# untitled.net
KiCad netlist of a schematic drawn in EAGLE
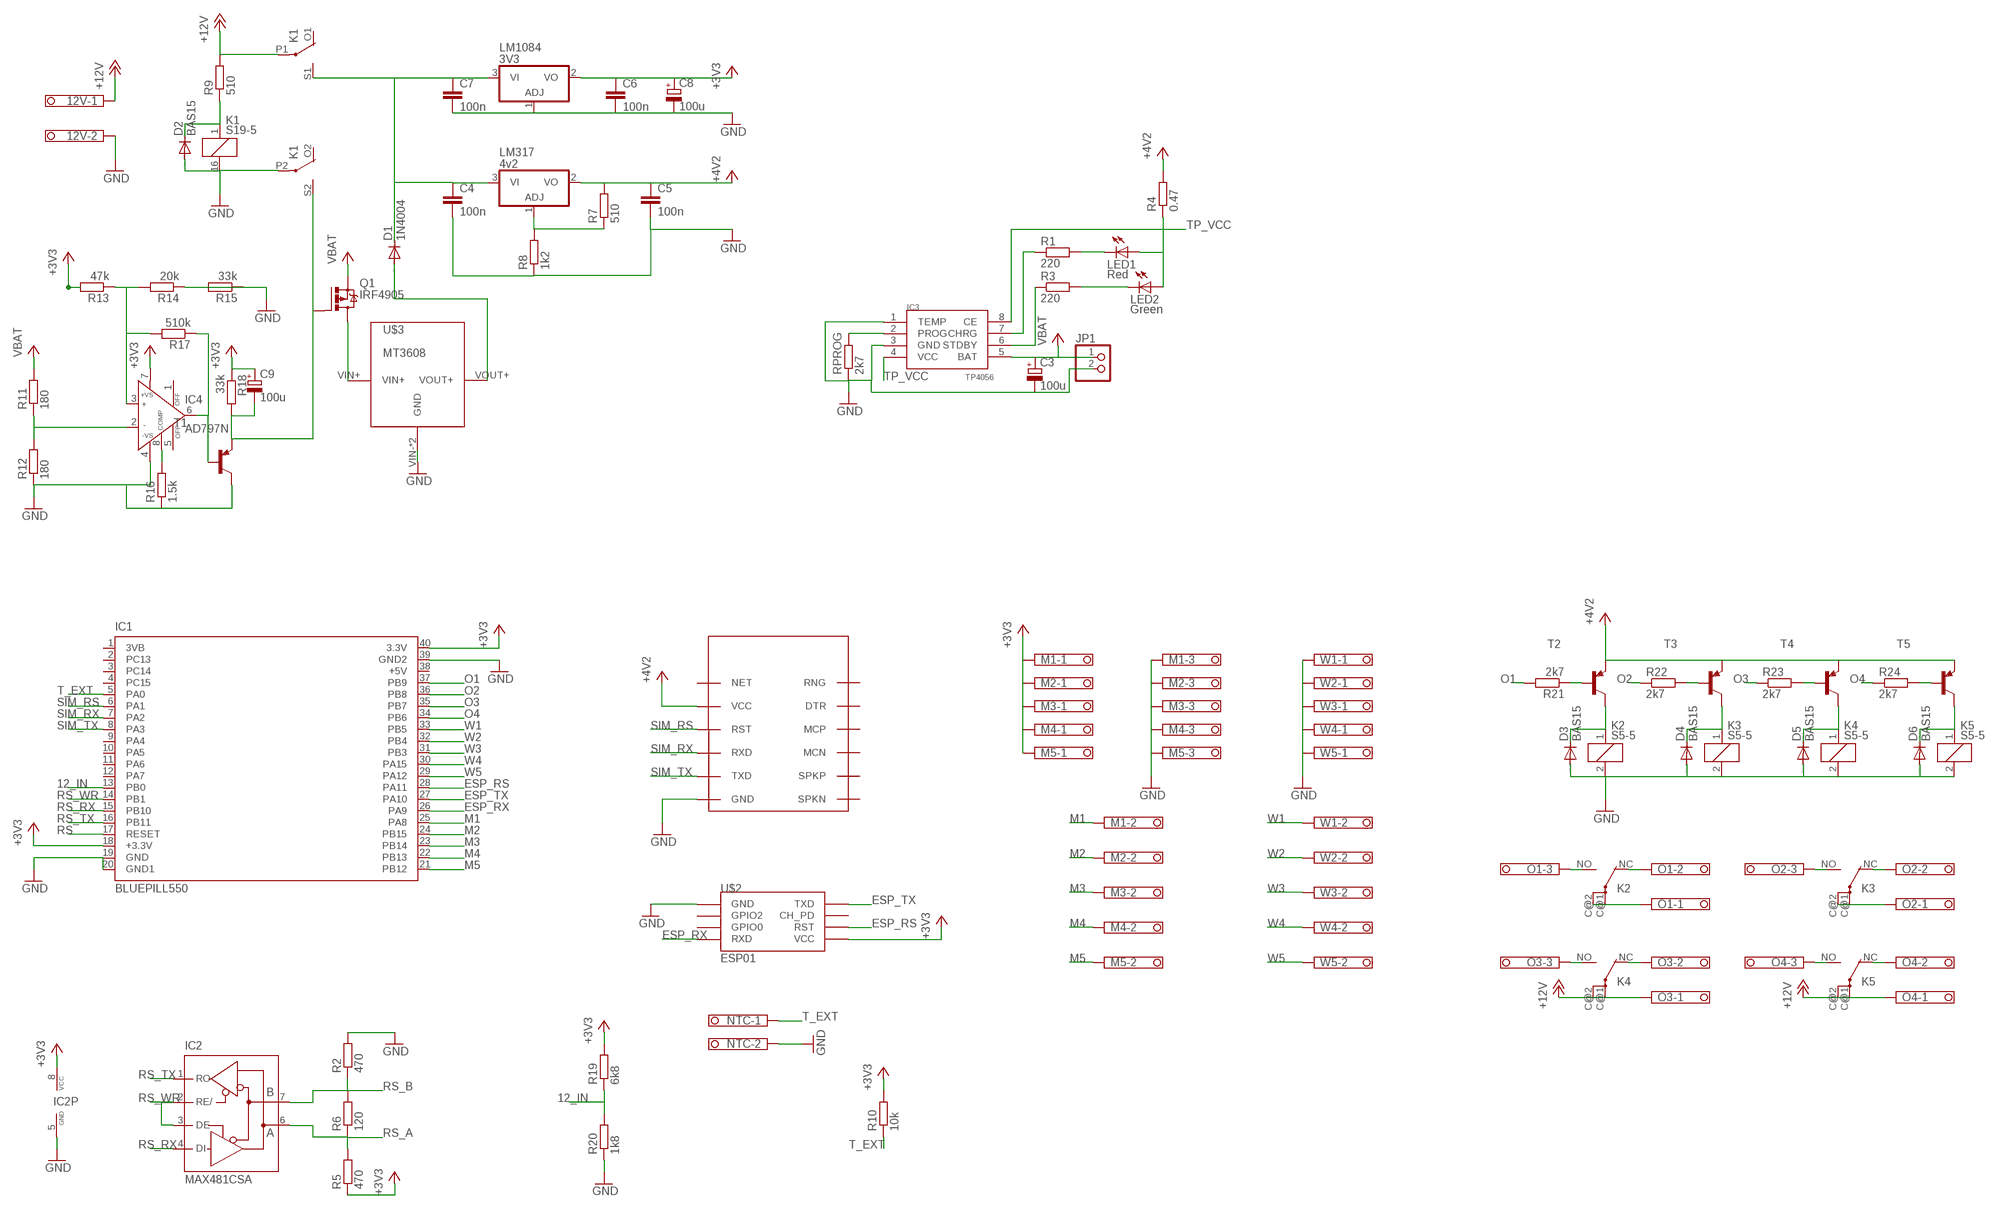
[diagram p0: schematic, sheet 1]

(export (version "E")
  (design (tool "Eeschema 10.0.6"))
  (components
    (comp (ref "12V")
      (value "1751248")
      (footprint "eagle-import:1751248")
      (libsource (lib "eagle-import") (part "1751248"))
    )
    (comp (ref "C3")
      (value "100u")
      (footprint "eagle-import:E2,5-6E")
      (libsource (lib "eagle-import") (part "CPOL-EUE2,5-6E"))
    )
    (comp (ref "C4")
      (value "100n")
      (footprint "eagle-import:C2012")
      (libsource (lib "eagle-import") (part "C-EUC2012"))
    )
    (comp (ref "C5")
      (value "100n")
      (footprint "eagle-import:C2012")
      (libsource (lib "eagle-import") (part "C-EUC2012"))
    )
    (comp (ref "C6")
      (value "100n")
      (footprint "eagle-import:C2012")
      (libsource (lib "eagle-import") (part "C-EUC2012"))
    )
    (comp (ref "C7")
      (value "100n")
      (footprint "eagle-import:C2012")
      (libsource (lib "eagle-import") (part "C-EUC2012"))
    )
    (comp (ref "C8")
      (value "100u")
      (footprint "eagle-import:E2,5-6E")
      (libsource (lib "eagle-import") (part "CPOL-EUE2,5-6E"))
    )
    (comp (ref "C9")
      (value "100u")
      (footprint "eagle-import:E2,5-6E")
      (libsource (lib "eagle-import") (part "CPOL-EUE2,5-6E"))
    )
    (comp (ref "D1")
      (value "1N4004")
      (footprint "eagle-import:DO41-10")
      (libsource (lib "eagle-import") (part "1N4004"))
    )
    (comp (ref "D2")
      (value "BAS15")
      (footprint "eagle-import:DO34-7")
      (libsource (lib "eagle-import") (part "BAS15"))
    )
    (comp (ref "D3")
      (value "BAS15")
      (footprint "eagle-import:DO34-7")
      (libsource (lib "eagle-import") (part "BAS15"))
    )
    (comp (ref "D4")
      (value "BAS15")
      (footprint "eagle-import:DO34-7")
      (libsource (lib "eagle-import") (part "BAS15"))
    )
    (comp (ref "D5")
      (value "BAS15")
      (footprint "eagle-import:DO34-7")
      (libsource (lib "eagle-import") (part "BAS15"))
    )
    (comp (ref "D6")
      (value "BAS15")
      (footprint "eagle-import:DO34-7")
      (libsource (lib "eagle-import") (part "BAS15"))
    )
    (comp (ref "IC1")
      (value "BLUEPILL550")
      (footprint "eagle-import:DIL40")
      (fields (field (name "MF") "BluePill"))
      (libsource (lib "eagle-import") (part "BLUEPILL550"))
    )
    (comp (ref "IC2")
      (value "MAX481CSA")
      (footprint "eagle-import:SO08")
      (fields (field (name "MF") "MAXIM"))
      (libsource (lib "eagle-import") (part "MAX481CSA"))
    )
    (comp (ref "IC3")
      (value "TP4056")
      (footprint "eagle-import:SOP-8")
      (libsource (lib "eagle-import") (part "TP4056"))
    )
    (comp (ref "IC4")
      (value "AD797N")
      (footprint "eagle-import:DIL08")
      (fields (field (name "MF") "ALTERA CORPORATION") (field (name "MPN") "AD797ANZ"))
      (libsource (lib "eagle-import") (part "AD797N"))
    )
    (comp (ref "JP1")
      (value "PINHD-1X2")
      (footprint "eagle-import:1X02")
      (libsource (lib "eagle-import") (part "PINHD-1X2"))
    )
    (comp (ref "K1")
      (value "S19-5")
      (footprint "eagle-import:351")
      (libsource (lib "eagle-import") (part "351"))
    )
    (comp (ref "K2")
      (value "S5-5")
      (footprint "eagle-import:HY")
      (fields (field (name "MF") "AROMAT/ MATSUSHITA") (field (name "MPN") "HY1-5V"))
      (libsource (lib "eagle-import") (part "HY1-5V"))
    )
    (comp (ref "K3")
      (value "S5-5")
      (footprint "eagle-import:HY")
      (fields (field (name "MF") "AROMAT/ MATSUSHITA") (field (name "MPN") "HY1-5V"))
      (libsource (lib "eagle-import") (part "HY1-5V"))
    )
    (comp (ref "K4")
      (value "S5-5")
      (footprint "eagle-import:HY")
      (fields (field (name "MF") "AROMAT/ MATSUSHITA") (field (name "MPN") "HY1-5V"))
      (libsource (lib "eagle-import") (part "HY1-5V"))
    )
    (comp (ref "K5")
      (value "S5-5")
      (footprint "eagle-import:HY")
      (fields (field (name "MF") "AROMAT/ MATSUSHITA") (field (name "MPN") "HY1-5V"))
      (libsource (lib "eagle-import") (part "HY1-5V"))
    )
    (comp (ref "LED1")
      (value "Red")
      (footprint "eagle-import:CHIP-LED0805")
      (libsource (lib "eagle-import") (part "LEDCHIP-LED0805"))
    )
    (comp (ref "LED2")
      (value "Green")
      (footprint "eagle-import:CHIP-LED0805")
      (libsource (lib "eagle-import") (part "LEDCHIP-LED0805"))
    )
    (comp (ref "LM317")
      (value "4v2")
      (footprint "eagle-import:TO220H")
      (libsource (lib "eagle-import") (part "317T"))
    )
    (comp (ref "LM1084")
      (value "3V3")
      (footprint "eagle-import:TO220H")
      (libsource (lib "eagle-import") (part "317T"))
    )
    (comp (ref "M1")
      (value "1751251")
      (footprint "eagle-import:1751251")
      (libsource (lib "eagle-import") (part "1751251"))
    )
    (comp (ref "M2")
      (value "1751251")
      (footprint "eagle-import:1751251")
      (libsource (lib "eagle-import") (part "1751251"))
    )
    (comp (ref "M3")
      (value "1751251")
      (footprint "eagle-import:1751251")
      (libsource (lib "eagle-import") (part "1751251"))
    )
    (comp (ref "M4")
      (value "1751251")
      (footprint "eagle-import:1751251")
      (libsource (lib "eagle-import") (part "1751251"))
    )
    (comp (ref "M5")
      (value "1751251")
      (footprint "eagle-import:1751251")
      (libsource (lib "eagle-import") (part "1751251"))
    )
    (comp (ref "NTC")
      (value "1751248")
      (footprint "eagle-import:1751248")
      (libsource (lib "eagle-import") (part "1751248"))
    )
    (comp (ref "O1")
      (value "1751251")
      (footprint "eagle-import:1751251")
      (libsource (lib "eagle-import") (part "1751251"))
    )
    (comp (ref "O2")
      (value "1751251")
      (footprint "eagle-import:1751251")
      (libsource (lib "eagle-import") (part "1751251"))
    )
    (comp (ref "O3")
      (value "1751251")
      (footprint "eagle-import:1751251")
      (libsource (lib "eagle-import") (part "1751251"))
    )
    (comp (ref "O4")
      (value "1751251")
      (footprint "eagle-import:1751251")
      (libsource (lib "eagle-import") (part "1751251"))
    )
    (comp (ref "Q1")
      (value "IRF4905")
      (footprint "eagle-import:TO220BH")
      (libsource (lib "eagle-import") (part "IRF4905"))
    )
    (comp (ref "R1")
      (value "220")
      (footprint "eagle-import:R0805")
      (libsource (lib "eagle-import") (part "resistor_R-EU_R0805"))
    )
    (comp (ref "R2")
      (value "470")
      (footprint "eagle-import:0204_5")
      (libsource (lib "eagle-import") (part "resistor_R-EU_0204/5"))
    )
    (comp (ref "R3")
      (value "220")
      (footprint "eagle-import:R0805")
      (libsource (lib "eagle-import") (part "resistor_R-EU_R0805"))
    )
    (comp (ref "R4")
      (value "0.47")
      (footprint "eagle-import:0207_12")
      (libsource (lib "eagle-import") (part "resistor_R-EU_0207/12"))
    )
    (comp (ref "R5")
      (value "470")
      (footprint "eagle-import:0204_5")
      (libsource (lib "eagle-import") (part "resistor_R-EU_0204/5"))
    )
    (comp (ref "R6")
      (value "120")
      (footprint "eagle-import:0204_7")
      (libsource (lib "eagle-import") (part "resistor_R-EU_0204/7"))
    )
    (comp (ref "R7")
      (value "510")
      (footprint "eagle-import:0204_7")
      (libsource (lib "eagle-import") (part "resistor_R-EU_0204/7"))
    )
    (comp (ref "R8")
      (value "1k2")
      (footprint "eagle-import:0204_7")
      (libsource (lib "eagle-import") (part "resistor_R-EU_0204/7"))
    )
    (comp (ref "R9")
      (value "510")
      (footprint "eagle-import:0204_7")
      (libsource (lib "eagle-import") (part "resistor_R-EU_0204/7"))
    )
    (comp (ref "R10")
      (value "10k")
      (footprint "eagle-import:0204_5")
      (libsource (lib "eagle-import") (part "R-EU_0204/5"))
    )
    (comp (ref "R11")
      (value "180")
      (footprint "eagle-import:0204_7")
      (libsource (lib "eagle-import") (part "resistor_R-EU_0204/7"))
    )
    (comp (ref "R12")
      (value "180")
      (footprint "eagle-import:0204_7")
      (libsource (lib "eagle-import") (part "resistor_R-EU_0204/7"))
    )
    (comp (ref "R13")
      (value "47k")
      (footprint "eagle-import:0204_7")
      (libsource (lib "eagle-import") (part "resistor_R-EU_0204/7"))
    )
    (comp (ref "R14")
      (value "20k")
      (footprint "eagle-import:0204_7")
      (libsource (lib "eagle-import") (part "resistor_R-EU_0204/7"))
    )
    (comp (ref "R15")
      (value "33k")
      (footprint "eagle-import:0204_7")
      (libsource (lib "eagle-import") (part "resistor_R-EU_0204/7"))
    )
    (comp (ref "R16")
      (value "1.5k")
      (footprint "eagle-import:0204_7")
      (libsource (lib "eagle-import") (part "resistor_R-EU_0204/7"))
    )
    (comp (ref "R17")
      (value "510k")
      (footprint "eagle-import:0204_7")
      (libsource (lib "eagle-import") (part "resistor_R-EU_0204/7"))
    )
    (comp (ref "R18")
      (value "33k")
      (footprint "eagle-import:0204_7")
      (libsource (lib "eagle-import") (part "resistor_R-EU_0204/7"))
    )
    (comp (ref "R19")
      (value "6k8")
      (footprint "eagle-import:0204_5")
      (libsource (lib "eagle-import") (part "R-EU_0204/5"))
    )
    (comp (ref "R20")
      (value "1k8")
      (footprint "eagle-import:0204_5")
      (libsource (lib "eagle-import") (part "R-EU_0204/5"))
    )
    (comp (ref "R21")
      (value "2k7")
      (footprint "eagle-import:0204_7")
      (libsource (lib "eagle-import") (part "resistor_R-EU_0204/7"))
    )
    (comp (ref "R22")
      (value "2k7")
      (footprint "eagle-import:0204_7")
      (libsource (lib "eagle-import") (part "resistor_R-EU_0204/7"))
    )
    (comp (ref "R23")
      (value "2k7")
      (footprint "eagle-import:0204_7")
      (libsource (lib "eagle-import") (part "resistor_R-EU_0204/7"))
    )
    (comp (ref "R24")
      (value "2k7")
      (footprint "eagle-import:0204_7")
      (libsource (lib "eagle-import") (part "resistor_R-EU_0204/7"))
    )
    (comp (ref "RPROG")
      (value "2k7")
      (footprint "eagle-import:0204_7")
      (libsource (lib "eagle-import") (part "resistor_R-EU_0204/7"))
    )
    (comp (ref "T1")
      (value "BC327-40-PNP-TO92-EBC")
      (footprint "eagle-import:TO92-EBC")
      (libsource (lib "eagle-import") (part "-PNP-TO92-EBCBC327-40"))
    )
    (comp (ref "T2")
      (value "BC327-40-PNP-TO92-EBC")
      (footprint "eagle-import:TO92-EBC")
      (libsource (lib "eagle-import") (part "-PNP-TO92-EBCBC327-40"))
    )
    (comp (ref "T3")
      (value "BC327-40-PNP-TO92-EBC")
      (footprint "eagle-import:TO92-EBC")
      (libsource (lib "eagle-import") (part "-PNP-TO92-EBCBC327-40"))
    )
    (comp (ref "T4")
      (value "BC327-40-PNP-TO92-EBC")
      (footprint "eagle-import:TO92-EBC")
      (libsource (lib "eagle-import") (part "-PNP-TO92-EBCBC327-40"))
    )
    (comp (ref "T5")
      (value "BC327-40-PNP-TO92-EBC")
      (footprint "eagle-import:TO92-EBC")
      (libsource (lib "eagle-import") (part "-PNP-TO92-EBCBC327-40"))
    )
    (comp (ref "U$1")
      (value "SIM800L")
      (footprint "eagle-import:SIM-CORE")
      (libsource (lib "eagle-import") (part "SIM800L"))
    )
    (comp (ref "U$2")
      (value "ESP01")
      (footprint "eagle-import:ESP01")
      (libsource (lib "eagle-import") (part "ESP01"))
    )
    (comp (ref "U$3")
      (value "MT3608")
      (footprint "eagle-import:MT3608")
      (libsource (lib "eagle-import") (part "MT3608"))
    )
    (comp (ref "W1")
      (value "1751248")
      (footprint "eagle-import:1751248")
      (libsource (lib "eagle-import") (part "1751248"))
    )
    (comp (ref "W2")
      (value "1751248")
      (footprint "eagle-import:1751248")
      (libsource (lib "eagle-import") (part "1751248"))
    )
    (comp (ref "W3")
      (value "1751248")
      (footprint "eagle-import:1751248")
      (libsource (lib "eagle-import") (part "1751248"))
    )
    (comp (ref "W4")
      (value "1751248")
      (footprint "eagle-import:1751248")
      (libsource (lib "eagle-import") (part "1751248"))
    )
    (comp (ref "W5")
      (value "1751248")
      (footprint "eagle-import:1751248")
      (libsource (lib "eagle-import") (part "1751248"))
    )
  )
  (nets
    (net (code "1") (name "+3V3") (class "Default")
      (node (ref "C6") (pin "1") (pinfunction "1_1") (pintype "passive"))
      (node (ref "C8") (pin "+") (pinfunction "+_+") (pintype "passive"))
      (node (ref "C9") (pin "+") (pinfunction "+_+") (pintype "passive"))
      (node (ref "IC1") (pin "18") (pinfunction "+3.3V_18") (pintype "bidirectional"))
      (node (ref "IC1") (pin "40") (pinfunction "3.3V_40") (pintype "bidirectional"))
      (node (ref "IC2") (pin "8") (pinfunction "VCC_8") (pintype "power_in"))
      (node (ref "IC4") (pin "7") (pinfunction "+VS_7") (pintype "input"))
      (node (ref "LM1084") (pin "2") (pinfunction "VO_2") (pintype "passive"))
      (node (ref "M1") (pin "1") (pinfunction "K_1") (pintype "passive"))
      (node (ref "M2") (pin "1") (pinfunction "K_1") (pintype "passive"))
      (node (ref "M3") (pin "1") (pinfunction "K_1") (pintype "passive"))
      (node (ref "M4") (pin "1") (pinfunction "K_1") (pintype "passive"))
      (node (ref "M5") (pin "1") (pinfunction "K_1") (pintype "passive"))
      (node (ref "R10") (pin "2") (pinfunction "2_2") (pintype "passive"))
      (node (ref "R13") (pin "2") (pinfunction "2_2") (pintype "passive"))
      (node (ref "R18") (pin "1") (pinfunction "1_1") (pintype "passive"))
      (node (ref "R19") (pin "2") (pinfunction "2_2") (pintype "passive"))
      (node (ref "R5") (pin "1") (pinfunction "1_1") (pintype "passive"))
      (node (ref "U$2") (pin "VCC") (pinfunction "VCC_VCC") (pintype "bidirectional"))
    )
    (net (code "2") (name "+4V2") (class "Default")
      (node (ref "C3") (pin "+") (pinfunction "+_+") (pintype "passive"))
      (node (ref "C5") (pin "1") (pinfunction "1_1") (pintype "passive"))
      (node (ref "IC3") (pin "5") (pinfunction "BAT_5") (pintype "bidirectional"))
      (node (ref "JP1") (pin "1") (pinfunction "1_1") (pintype "passive"))
      (node (ref "LM317") (pin "2") (pinfunction "VO_2") (pintype "passive"))
      (node (ref "Q1") (pin "S") (pinfunction "S_S") (pintype "passive"))
      (node (ref "R11") (pin "2") (pinfunction "2_2") (pintype "passive"))
      (node (ref "R4") (pin "2") (pinfunction "2_2") (pintype "passive"))
      (node (ref "R7") (pin "2") (pinfunction "2_2") (pintype "passive"))
      (node (ref "T2") (pin "E") (pinfunction "E_E") (pintype "passive"))
      (node (ref "T3") (pin "E") (pinfunction "E_E") (pintype "passive"))
      (node (ref "T4") (pin "E") (pinfunction "E_E") (pintype "passive"))
      (node (ref "T5") (pin "E") (pinfunction "E_E") (pintype "passive"))
      (node (ref "U$1") (pin "VCC") (pinfunction "VCC_VCC") (pintype "bidirectional"))
    )
    (net (code "3") (name "+12V") (class "Default")
      (node (ref "12V") (pin "1") (pinfunction "K_1") (pintype "passive"))
      (node (ref "K1") (pin "P1") (pinfunction "P_P1") (pintype "passive"))
      (node (ref "K4") (pin "C@1") (pinfunction "P_C@1") (pintype "passive"))
      (node (ref "K4") (pin "C@2") (pinfunction "P_C@2") (pintype "passive"))
      (node (ref "K5") (pin "C@1") (pinfunction "P_C@1") (pintype "passive"))
      (node (ref "K5") (pin "C@2") (pinfunction "P_C@2") (pintype "passive"))
      (node (ref "O3") (pin "1") (pinfunction "K_1") (pintype "passive"))
      (node (ref "O4") (pin "1") (pinfunction "K_1") (pintype "passive"))
      (node (ref "R9") (pin "2") (pinfunction "2_2") (pintype "passive"))
    )
    (net (code "4") (name "/12_IN") (class "Default")
      (node (ref "IC1") (pin "13") (pinfunction "PB0_13") (pintype "input"))
      (node (ref "R19") (pin "1") (pinfunction "1_1") (pintype "passive"))
      (node (ref "R20") (pin "2") (pinfunction "2_2") (pintype "passive"))
    )
    (net (code "5") (name "/ESP_RS") (class "Default")
      (node (ref "IC1") (pin "28") (pinfunction "PA11_28") (pintype "bidirectional"))
      (node (ref "U$2") (pin "RST") (pinfunction "RST_RST") (pintype "bidirectional"))
    )
    (net (code "6") (name "/ESP_RX") (class "Default")
      (node (ref "IC1") (pin "26") (pinfunction "PA9_26") (pintype "bidirectional"))
      (node (ref "U$2") (pin "RX") (pinfunction "RXD_RX") (pintype "bidirectional"))
    )
    (net (code "7") (name "/ESP_TX") (class "Default")
      (node (ref "IC1") (pin "27") (pinfunction "PA10_27") (pintype "bidirectional"))
      (node (ref "U$2") (pin "TX") (pinfunction "TXD_TX") (pintype "bidirectional"))
    )
    (net (code "8") (name "/M1") (class "Default")
      (node (ref "IC1") (pin "25") (pinfunction "PA8_25") (pintype "bidirectional"))
      (node (ref "M1") (pin "2") (pinfunction "K_2") (pintype "passive"))
    )
    (net (code "9") (name "/M2") (class "Default")
      (node (ref "IC1") (pin "24") (pinfunction "PB15_24") (pintype "bidirectional"))
      (node (ref "M2") (pin "2") (pinfunction "K_2") (pintype "passive"))
    )
    (net (code "10") (name "/M3") (class "Default")
      (node (ref "IC1") (pin "23") (pinfunction "PB14_23") (pintype "bidirectional"))
      (node (ref "M3") (pin "2") (pinfunction "K_2") (pintype "passive"))
    )
    (net (code "11") (name "/M4") (class "Default")
      (node (ref "IC1") (pin "22") (pinfunction "PB13_22") (pintype "bidirectional"))
      (node (ref "M4") (pin "2") (pinfunction "K_2") (pintype "passive"))
    )
    (net (code "12") (name "/M5") (class "Default")
      (node (ref "IC1") (pin "21") (pinfunction "PB12_21") (pintype "bidirectional"))
      (node (ref "M5") (pin "2") (pinfunction "K_2") (pintype "passive"))
    )
    (net (code "13") (name "/O1") (class "Default")
      (node (ref "IC1") (pin "37") (pinfunction "PB9_37") (pintype "bidirectional"))
      (node (ref "R21") (pin "2") (pinfunction "2_2") (pintype "passive"))
    )
    (net (code "14") (name "/O2") (class "Default")
      (node (ref "IC1") (pin "36") (pinfunction "PB8_36") (pintype "bidirectional"))
      (node (ref "R22") (pin "1") (pinfunction "1_1") (pintype "passive"))
    )
    (net (code "15") (name "/O3") (class "Default")
      (node (ref "IC1") (pin "35") (pinfunction "PB7_35") (pintype "bidirectional"))
      (node (ref "R23") (pin "1") (pinfunction "1_1") (pintype "passive"))
    )
    (net (code "16") (name "/O4") (class "Default")
      (node (ref "IC1") (pin "34") (pinfunction "PB6_34") (pintype "bidirectional"))
      (node (ref "R24") (pin "1") (pinfunction "1_1") (pintype "passive"))
    )
    (net (code "17") (name "/PA6") (class "Default")
      (node (ref "IC1") (pin "11") (pinfunction "PA6_11") (pintype "power_in"))
    )
    (net (code "18") (name "/PA7") (class "Default")
      (node (ref "IC1") (pin "12") (pinfunction "PA7_12") (pintype "power_in"))
    )
    (net (code "19") (name "/RS") (class "Default")
      (node (ref "IC1") (pin "17") (pinfunction "RESET_17") (pintype "bidirectional"))
    )
    (net (code "20") (name "/RS_A") (class "Default")
      (node (ref "IC2") (pin "6") (pinfunction "A_6") (pintype "passive"))
      (node (ref "R5") (pin "2") (pinfunction "2_2") (pintype "passive"))
      (node (ref "R6") (pin "1") (pinfunction "1_1") (pintype "passive"))
    )
    (net (code "21") (name "/RS_B") (class "Default")
      (node (ref "IC2") (pin "7") (pinfunction "B_7") (pintype "passive"))
      (node (ref "R2") (pin "1") (pinfunction "1_1") (pintype "passive"))
      (node (ref "R6") (pin "2") (pinfunction "2_2") (pintype "passive"))
    )
    (net (code "22") (name "/RS_RX") (class "Default")
      (node (ref "IC1") (pin "15") (pinfunction "PB10_15") (pintype "bidirectional"))
      (node (ref "IC2") (pin "4") (pinfunction "DI_4") (pintype "input"))
    )
    (net (code "23") (name "/RS_TX") (class "Default")
      (node (ref "IC1") (pin "16") (pinfunction "PB11_16") (pintype "bidirectional"))
      (node (ref "IC2") (pin "1") (pinfunction "RO_1") (pintype "output"))
    )
    (net (code "24") (name "/RS_WR") (class "Default")
      (node (ref "IC1") (pin "14") (pinfunction "PB1_14") (pintype "output"))
      (node (ref "IC2") (pin "2") (pinfunction "RE/_2") (pintype "input"))
      (node (ref "IC2") (pin "3") (pinfunction "DE_3") (pintype "input"))
    )
    (net (code "25") (name "/SIM_RS") (class "Default")
      (node (ref "IC1") (pin "6") (pinfunction "PA1_6") (pintype "bidirectional"))
      (node (ref "U$1") (pin "RST") (pinfunction "RST_RST") (pintype "bidirectional"))
    )
    (net (code "26") (name "/SIM_RX") (class "Default")
      (node (ref "IC1") (pin "7") (pinfunction "PA2_7") (pintype "bidirectional"))
      (node (ref "U$1") (pin "RXD") (pinfunction "RXD_RXD") (pintype "bidirectional"))
    )
    (net (code "27") (name "/SIM_TX") (class "Default")
      (node (ref "IC1") (pin "8") (pinfunction "PA3_8") (pintype "bidirectional"))
      (node (ref "U$1") (pin "TXD") (pinfunction "TXD_TXD") (pintype "bidirectional"))
    )
    (net (code "28") (name "/TP_VCC") (class "Default")
      (node (ref "IC3") (pin "4") (pinfunction "VCC_4") (pintype "bidirectional"))
      (node (ref "IC3") (pin "8") (pinfunction "CE_8") (pintype "bidirectional"))
      (node (ref "LED1") (pin "A") (pinfunction "A_A") (pintype "passive"))
      (node (ref "LED2") (pin "A") (pinfunction "A_A") (pintype "passive"))
      (node (ref "R4") (pin "1") (pinfunction "1_1") (pintype "passive"))
    )
    (net (code "29") (name "/T_EXT") (class "Default")
      (node (ref "IC1") (pin "5") (pinfunction "PA0_5") (pintype "bidirectional"))
      (node (ref "NTC") (pin "1") (pinfunction "K_1") (pintype "passive"))
      (node (ref "R10") (pin "1") (pinfunction "1_1") (pintype "passive"))
    )
    (net (code "30") (name "/W1") (class "Default")
      (node (ref "IC1") (pin "33") (pinfunction "PB5_33") (pintype "bidirectional"))
      (node (ref "W1") (pin "2") (pinfunction "K_2") (pintype "passive"))
    )
    (net (code "31") (name "/W2") (class "Default")
      (node (ref "IC1") (pin "32") (pinfunction "PB4_32") (pintype "power_in"))
      (node (ref "W2") (pin "2") (pinfunction "K_2") (pintype "passive"))
    )
    (net (code "32") (name "/W3") (class "Default")
      (node (ref "IC1") (pin "31") (pinfunction "PB3_31") (pintype "power_in"))
      (node (ref "W3") (pin "2") (pinfunction "K_2") (pintype "passive"))
    )
    (net (code "33") (name "/W4") (class "Default")
      (node (ref "IC1") (pin "30") (pinfunction "PA15_30") (pintype "bidirectional"))
      (node (ref "W4") (pin "2") (pinfunction "K_2") (pintype "passive"))
    )
    (net (code "34") (name "/W5") (class "Default")
      (node (ref "IC1") (pin "29") (pinfunction "PA12_29") (pintype "bidirectional"))
      (node (ref "W5") (pin "2") (pinfunction "K_2") (pintype "passive"))
    )
    (net (code "35") (name "GND") (class "Default")
      (node (ref "12V") (pin "2") (pinfunction "K_2") (pintype "passive"))
      (node (ref "C3") (pin "-") (pinfunction "-_-") (pintype "passive"))
      (node (ref "C4") (pin "2") (pinfunction "2_2") (pintype "passive"))
      (node (ref "C5") (pin "2") (pinfunction "2_2") (pintype "passive"))
      (node (ref "C6") (pin "2") (pinfunction "2_2") (pintype "passive"))
      (node (ref "C7") (pin "2") (pinfunction "2_2") (pintype "passive"))
      (node (ref "C8") (pin "-") (pinfunction "-_-") (pintype "passive"))
      (node (ref "D2") (pin "A") (pinfunction "A_A") (pintype "passive"))
      (node (ref "D3") (pin "A") (pinfunction "A_A") (pintype "passive"))
      (node (ref "D4") (pin "A") (pinfunction "A_A") (pintype "passive"))
      (node (ref "D5") (pin "A") (pinfunction "A_A") (pintype "passive"))
      (node (ref "D6") (pin "A") (pinfunction "A_A") (pintype "passive"))
      (node (ref "IC1") (pin "19") (pinfunction "GND_19") (pintype "bidirectional"))
      (node (ref "IC1") (pin "20") (pinfunction "GND1_20") (pintype "bidirectional"))
      (node (ref "IC1") (pin "39") (pinfunction "GND2_39") (pintype "bidirectional"))
      (node (ref "IC2") (pin "5") (pinfunction "GND_5") (pintype "power_in"))
      (node (ref "IC3") (pin "1") (pinfunction "TEMP_1") (pintype "bidirectional"))
      (node (ref "IC3") (pin "3") (pinfunction "GND_3") (pintype "bidirectional"))
      (node (ref "IC4") (pin "4") (pinfunction "-VS_4") (pintype "input"))
      (node (ref "JP1") (pin "2") (pinfunction "2_2") (pintype "passive"))
      (node (ref "K1") (pin "16") (pinfunction "2_16") (pintype "passive"))
      (node (ref "K1") (pin "P2") (pinfunction "P_P2") (pintype "passive"))
      (node (ref "K2") (pin "2") (pinfunction "2_2") (pintype "passive"))
      (node (ref "K3") (pin "2") (pinfunction "2_2") (pintype "passive"))
      (node (ref "K4") (pin "2") (pinfunction "2_2") (pintype "passive"))
      (node (ref "K5") (pin "2") (pinfunction "2_2") (pintype "passive"))
      (node (ref "LM1084") (pin "1") (pinfunction "ADJ_1") (pintype "input"))
      (node (ref "M1") (pin "3") (pinfunction "K_3") (pintype "passive"))
      (node (ref "M2") (pin "3") (pinfunction "K_3") (pintype "passive"))
      (node (ref "M3") (pin "3") (pinfunction "K_3") (pintype "passive"))
      (node (ref "M4") (pin "3") (pinfunction "K_3") (pintype "passive"))
      (node (ref "M5") (pin "3") (pinfunction "K_3") (pintype "passive"))
      (node (ref "NTC") (pin "2") (pinfunction "K_2") (pintype "passive"))
      (node (ref "R12") (pin "1") (pinfunction "1_1") (pintype "passive"))
      (node (ref "R14") (pin "1") (pinfunction "1_1") (pintype "passive"))
      (node (ref "R15") (pin "1") (pinfunction "1_1") (pintype "passive"))
      (node (ref "R15") (pin "2") (pinfunction "2_2") (pintype "passive"))
      (node (ref "R16") (pin "1") (pinfunction "1_1") (pintype "passive"))
      (node (ref "R2") (pin "2") (pinfunction "2_2") (pintype "passive"))
      (node (ref "R20") (pin "1") (pinfunction "1_1") (pintype "passive"))
      (node (ref "R8") (pin "1") (pinfunction "1_1") (pintype "passive"))
      (node (ref "RPROG") (pin "1") (pinfunction "1_1") (pintype "passive"))
      (node (ref "T1") (pin "C") (pinfunction "C_C") (pintype "passive"))
      (node (ref "U$1") (pin "GND") (pinfunction "GND_GND") (pintype "bidirectional"))
      (node (ref "U$2") (pin "GND") (pinfunction "GND_GND") (pintype "bidirectional"))
      (node (ref "U$3") (pin "VIN-") (pinfunction "GND_VIN-") (pintype "power_in"))
      (node (ref "U$3") (pin "VOUT-") (pinfunction "GND_VOUT-") (pintype "power_in"))
      (node (ref "W1") (pin "1") (pinfunction "K_1") (pintype "passive"))
      (node (ref "W2") (pin "1") (pinfunction "K_1") (pintype "passive"))
      (node (ref "W3") (pin "1") (pinfunction "K_1") (pintype "passive"))
      (node (ref "W4") (pin "1") (pinfunction "K_1") (pintype "passive"))
      (node (ref "W5") (pin "1") (pinfunction "K_1") (pintype "passive"))
    )
    (net (code "36") (name "Net-(D1-PadA)") (class "Default")
      (node (ref "D1") (pin "A") (pinfunction "A_A") (pintype "passive"))
      (node (ref "U$3") (pin "VOUT+") (pinfunction "VOUT+_VOUT+") (pintype "power_in"))
    )
    (net (code "37") (name "Net-(D2-PadC)") (class "Default")
      (node (ref "D2") (pin "C") (pinfunction "C_C") (pintype "passive"))
      (node (ref "K1") (pin "1") (pinfunction "1_1") (pintype "passive"))
      (node (ref "R9") (pin "1") (pinfunction "1_1") (pintype "passive"))
    )
    (net (code "38") (name "Net-(D3-PadC)") (class "Default")
      (node (ref "D3") (pin "C") (pinfunction "C_C") (pintype "passive"))
      (node (ref "K2") (pin "1") (pinfunction "1_1") (pintype "passive"))
      (node (ref "T2") (pin "C") (pinfunction "C_C") (pintype "passive"))
    )
    (net (code "39") (name "Net-(D4-PadC)") (class "Default")
      (node (ref "D4") (pin "C") (pinfunction "C_C") (pintype "passive"))
      (node (ref "K3") (pin "1") (pinfunction "1_1") (pintype "passive"))
      (node (ref "T3") (pin "C") (pinfunction "C_C") (pintype "passive"))
    )
    (net (code "40") (name "Net-(D5-PadC)") (class "Default")
      (node (ref "D5") (pin "C") (pinfunction "C_C") (pintype "passive"))
      (node (ref "K4") (pin "1") (pinfunction "1_1") (pintype "passive"))
      (node (ref "T4") (pin "C") (pinfunction "C_C") (pintype "passive"))
    )
    (net (code "41") (name "Net-(D6-PadC)") (class "Default")
      (node (ref "D6") (pin "C") (pinfunction "C_C") (pintype "passive"))
      (node (ref "K5") (pin "1") (pinfunction "1_1") (pintype "passive"))
      (node (ref "T5") (pin "C") (pinfunction "C_C") (pintype "passive"))
    )
    (net (code "42") (name "Net-(IC3-CHRG)") (class "Default")
      (node (ref "IC3") (pin "7") (pinfunction "CHRG_7") (pintype "bidirectional"))
      (node (ref "R1") (pin "1") (pinfunction "1_1") (pintype "passive"))
    )
    (net (code "43") (name "Net-(IC3-PROG)") (class "Default")
      (node (ref "IC3") (pin "2") (pinfunction "PROG_2") (pintype "bidirectional"))
      (node (ref "RPROG") (pin "2") (pinfunction "2_2") (pintype "passive"))
    )
    (net (code "44") (name "Net-(IC3-STDBY)") (class "Default")
      (node (ref "IC3") (pin "6") (pinfunction "STDBY_6") (pintype "bidirectional"))
      (node (ref "R3") (pin "1") (pinfunction "1_1") (pintype "passive"))
    )
    (net (code "45") (name "Net-(IC4-COMP)") (class "Default")
      (node (ref "IC4") (pin "8") (pinfunction "COMP_8") (pintype "passive"))
      (node (ref "R16") (pin "2") (pinfunction "2_2") (pintype "passive"))
    )
    (net (code "46") (name "Net-(IC4-IN+)") (class "Default")
      (node (ref "IC4") (pin "3") (pinfunction "IN+_3") (pintype "input"))
      (node (ref "R13") (pin "1") (pinfunction "1_1") (pintype "passive"))
      (node (ref "R14") (pin "2") (pinfunction "2_2") (pintype "passive"))
      (node (ref "R17") (pin "2") (pinfunction "2_2") (pintype "passive"))
    )
    (net (code "47") (name "Net-(IC4-IN-)") (class "Default")
      (node (ref "IC4") (pin "2") (pinfunction "IN-_2") (pintype "input"))
      (node (ref "R11") (pin "1") (pinfunction "1_1") (pintype "passive"))
      (node (ref "R12") (pin "2") (pinfunction "2_2") (pintype "passive"))
    )
    (net (code "48") (name "Net-(IC4-OUT)") (class "Default")
      (node (ref "IC4") (pin "6") (pinfunction "OUT_6") (pintype "output"))
      (node (ref "R17") (pin "1") (pinfunction "1_1") (pintype "passive"))
      (node (ref "T1") (pin "B") (pinfunction "B_B") (pintype "passive"))
    )
    (net (code "49") (name "Net-(K1B-S)") (class "Default")
      (node (ref "C4") (pin "1") (pinfunction "1_1") (pintype "passive"))
      (node (ref "C7") (pin "1") (pinfunction "1_1") (pintype "passive"))
      (node (ref "D1") (pin "C") (pinfunction "C_C") (pintype "passive"))
      (node (ref "K1") (pin "S1") (pinfunction "S_S1") (pintype "passive"))
      (node (ref "LM1084") (pin "3") (pinfunction "VI_3") (pintype "input"))
      (node (ref "LM317") (pin "3") (pinfunction "VI_3") (pintype "input"))
    )
    (net (code "50") (name "Net-(K1C-S)") (class "Default")
      (node (ref "C9") (pin "-") (pinfunction "-_-") (pintype "passive"))
      (node (ref "K1") (pin "S2") (pinfunction "S_S2") (pintype "passive"))
      (node (ref "Q1") (pin "G") (pinfunction "G_G") (pintype "passive"))
      (node (ref "R18") (pin "2") (pinfunction "2_2") (pintype "passive"))
      (node (ref "T1") (pin "E") (pinfunction "E_E") (pintype "passive"))
    )
    (net (code "51") (name "Net-(K2B-O)") (class "Default")
      (node (ref "K2") (pin "NC") (pinfunction "O_NC") (pintype "passive"))
      (node (ref "O1") (pin "2") (pinfunction "K_2") (pintype "passive"))
    )
    (net (code "52") (name "Net-(K2B-S)") (class "Default")
      (node (ref "K2") (pin "NO") (pinfunction "S_NO") (pintype "passive"))
      (node (ref "O1") (pin "3") (pinfunction "K_3") (pintype "passive"))
    )
    (net (code "53") (name "Net-(K3B-O)") (class "Default")
      (node (ref "K3") (pin "NC") (pinfunction "O_NC") (pintype "passive"))
      (node (ref "O2") (pin "2") (pinfunction "K_2") (pintype "passive"))
    )
    (net (code "54") (name "Net-(K3B-S)") (class "Default")
      (node (ref "K3") (pin "NO") (pinfunction "S_NO") (pintype "passive"))
      (node (ref "O2") (pin "3") (pinfunction "K_3") (pintype "passive"))
    )
    (net (code "55") (name "Net-(K4B-O)") (class "Default")
      (node (ref "K4") (pin "NC") (pinfunction "O_NC") (pintype "passive"))
      (node (ref "O3") (pin "2") (pinfunction "K_2") (pintype "passive"))
    )
    (net (code "56") (name "Net-(K4B-S)") (class "Default")
      (node (ref "K4") (pin "NO") (pinfunction "S_NO") (pintype "passive"))
      (node (ref "O3") (pin "3") (pinfunction "K_3") (pintype "passive"))
    )
    (net (code "57") (name "Net-(K5B-O)") (class "Default")
      (node (ref "K5") (pin "NC") (pinfunction "O_NC") (pintype "passive"))
      (node (ref "O4") (pin "2") (pinfunction "K_2") (pintype "passive"))
    )
    (net (code "58") (name "Net-(K5B-S)") (class "Default")
      (node (ref "K5") (pin "NO") (pinfunction "S_NO") (pintype "passive"))
      (node (ref "O4") (pin "3") (pinfunction "K_3") (pintype "passive"))
    )
    (net (code "59") (name "Net-(LED1-PadC)") (class "Default")
      (node (ref "LED1") (pin "C") (pinfunction "C_C") (pintype "passive"))
      (node (ref "R1") (pin "2") (pinfunction "2_2") (pintype "passive"))
    )
    (net (code "60") (name "Net-(LED2-PadC)") (class "Default")
      (node (ref "LED2") (pin "C") (pinfunction "C_C") (pintype "passive"))
      (node (ref "R3") (pin "2") (pinfunction "2_2") (pintype "passive"))
    )
    (net (code "61") (name "Net-(LM317-ADJ)") (class "Default")
      (node (ref "LM317") (pin "1") (pinfunction "ADJ_1") (pintype "input"))
      (node (ref "R7") (pin "1") (pinfunction "1_1") (pintype "passive"))
      (node (ref "R8") (pin "2") (pinfunction "2_2") (pintype "passive"))
    )
    (net (code "62") (name "Net-(O1A-K)") (class "Default")
      (node (ref "K2") (pin "C@1") (pinfunction "P_C@1") (pintype "passive"))
      (node (ref "K2") (pin "C@2") (pinfunction "P_C@2") (pintype "passive"))
      (node (ref "O1") (pin "1") (pinfunction "K_1") (pintype "passive"))
    )
    (net (code "63") (name "Net-(O2A-K)") (class "Default")
      (node (ref "K3") (pin "C@1") (pinfunction "P_C@1") (pintype "passive"))
      (node (ref "K3") (pin "C@2") (pinfunction "P_C@2") (pintype "passive"))
      (node (ref "O2") (pin "1") (pinfunction "K_1") (pintype "passive"))
    )
    (net (code "64") (name "Net-(Q1-PadD)") (class "Default")
      (node (ref "Q1") (pin "D") (pinfunction "D_D") (pintype "passive"))
      (node (ref "U$3") (pin "VIN+") (pinfunction "VIN+_VIN+") (pintype "power_in"))
    )
    (net (code "65") (name "Net-(R21-Pad1)") (class "Default")
      (node (ref "R21") (pin "1") (pinfunction "1_1") (pintype "passive"))
      (node (ref "T2") (pin "B") (pinfunction "B_B") (pintype "passive"))
    )
    (net (code "66") (name "Net-(R22-Pad2)") (class "Default")
      (node (ref "R22") (pin "2") (pinfunction "2_2") (pintype "passive"))
      (node (ref "T3") (pin "B") (pinfunction "B_B") (pintype "passive"))
    )
    (net (code "67") (name "Net-(R23-Pad2)") (class "Default")
      (node (ref "R23") (pin "2") (pinfunction "2_2") (pintype "passive"))
      (node (ref "T4") (pin "B") (pinfunction "B_B") (pintype "passive"))
    )
    (net (code "68") (name "Net-(R24-Pad2)") (class "Default")
      (node (ref "R24") (pin "2") (pinfunction "2_2") (pintype "passive"))
      (node (ref "T5") (pin "B") (pinfunction "B_B") (pintype "passive"))
    )
    (net (code "69") (name "unconnected-(IC1-+5V-Pad38)") (class "Default")
      (node (ref "IC1") (pin "38") (pinfunction "+5V_38") (pintype "bidirectional"))
    )
    (net (code "70") (name "unconnected-(IC1-3VB-Pad1)") (class "Default")
      (node (ref "IC1") (pin "1") (pinfunction "3VB_1") (pintype "input"))
    )
    (net (code "71") (name "unconnected-(IC1-PA4-Pad9)") (class "Default")
      (node (ref "IC1") (pin "9") (pinfunction "PA4_9") (pintype "bidirectional"))
    )
    (net (code "72") (name "unconnected-(IC1-PA5-Pad10)") (class "Default")
      (node (ref "IC1") (pin "10") (pinfunction "PA5_10") (pintype "bidirectional"))
    )
    (net (code "73") (name "unconnected-(IC1-PC13-Pad2)") (class "Default")
      (node (ref "IC1") (pin "2") (pinfunction "PC13_2") (pintype "bidirectional"))
    )
    (net (code "74") (name "unconnected-(IC1-PC14-Pad3)") (class "Default")
      (node (ref "IC1") (pin "3") (pinfunction "PC14_3") (pintype "bidirectional"))
    )
    (net (code "75") (name "unconnected-(IC1-PC15-Pad4)") (class "Default")
      (node (ref "IC1") (pin "4") (pinfunction "PC15_4") (pintype "bidirectional"))
    )
    (net (code "76") (name "unconnected-(IC4-OFF-Pad1)") (class "Default")
      (node (ref "IC4") (pin "1") (pinfunction "OFF_1") (pintype "passive"))
    )
    (net (code "77") (name "unconnected-(IC4-OFF-Pad5)") (class "Default")
      (node (ref "IC4") (pin "5") (pinfunction "OFF_5") (pintype "passive"))
    )
    (net (code "78") (name "unconnected-(K1B-O-PadO1)") (class "Default")
      (node (ref "K1") (pin "O1") (pinfunction "O_O1") (pintype "passive"))
    )
    (net (code "79") (name "unconnected-(K1C-O-PadO2)") (class "Default")
      (node (ref "K1") (pin "O2") (pinfunction "O_O2") (pintype "passive"))
    )
    (net (code "80") (name "unconnected-(U$1-PadDTR)") (class "Default")
      (node (ref "U$1") (pin "DTR") (pinfunction "DTR_DTR") (pintype "bidirectional"))
    )
    (net (code "81") (name "unconnected-(U$1-PadMCN)") (class "Default")
      (node (ref "U$1") (pin "MCN") (pinfunction "MCN_MCN") (pintype "bidirectional"))
    )
    (net (code "82") (name "unconnected-(U$1-PadMCP)") (class "Default")
      (node (ref "U$1") (pin "MCP") (pinfunction "MCP_MCP") (pintype "bidirectional"))
    )
    (net (code "83") (name "unconnected-(U$1-PadNET)") (class "Default")
      (node (ref "U$1") (pin "NET") (pinfunction "NET_NET") (pintype "bidirectional"))
    )
    (net (code "84") (name "unconnected-(U$1-PadRNG)") (class "Default")
      (node (ref "U$1") (pin "RNG") (pinfunction "RNG_RNG") (pintype "bidirectional"))
    )
    (net (code "85") (name "unconnected-(U$1-PadSPKN)") (class "Default")
      (node (ref "U$1") (pin "SPKN") (pinfunction "SPKN_SPKN") (pintype "bidirectional"))
    )
    (net (code "86") (name "unconnected-(U$1-PadSPKP)") (class "Default")
      (node (ref "U$1") (pin "SPKP") (pinfunction "SPKP_SPKP") (pintype "bidirectional"))
    )
    (net (code "87") (name "unconnected-(U$2-PadCH_PD)") (class "Default")
      (node (ref "U$2") (pin "CH_PD") (pinfunction "CH_PD_CH_PD") (pintype "bidirectional"))
    )
    (net (code "88") (name "unconnected-(U$2-PadGPIO0)") (class "Default")
      (node (ref "U$2") (pin "GPIO0") (pinfunction "GPIO0_GPIO0") (pintype "bidirectional"))
    )
    (net (code "89") (name "unconnected-(U$2-PadGPIO2)") (class "Default")
      (node (ref "U$2") (pin "GPIO2") (pinfunction "GPIO2_GPIO2") (pintype "bidirectional"))
    )
  )
)
